# dc-motor-driver.net
KiCad netlist of a schematic drawn in EAGLE
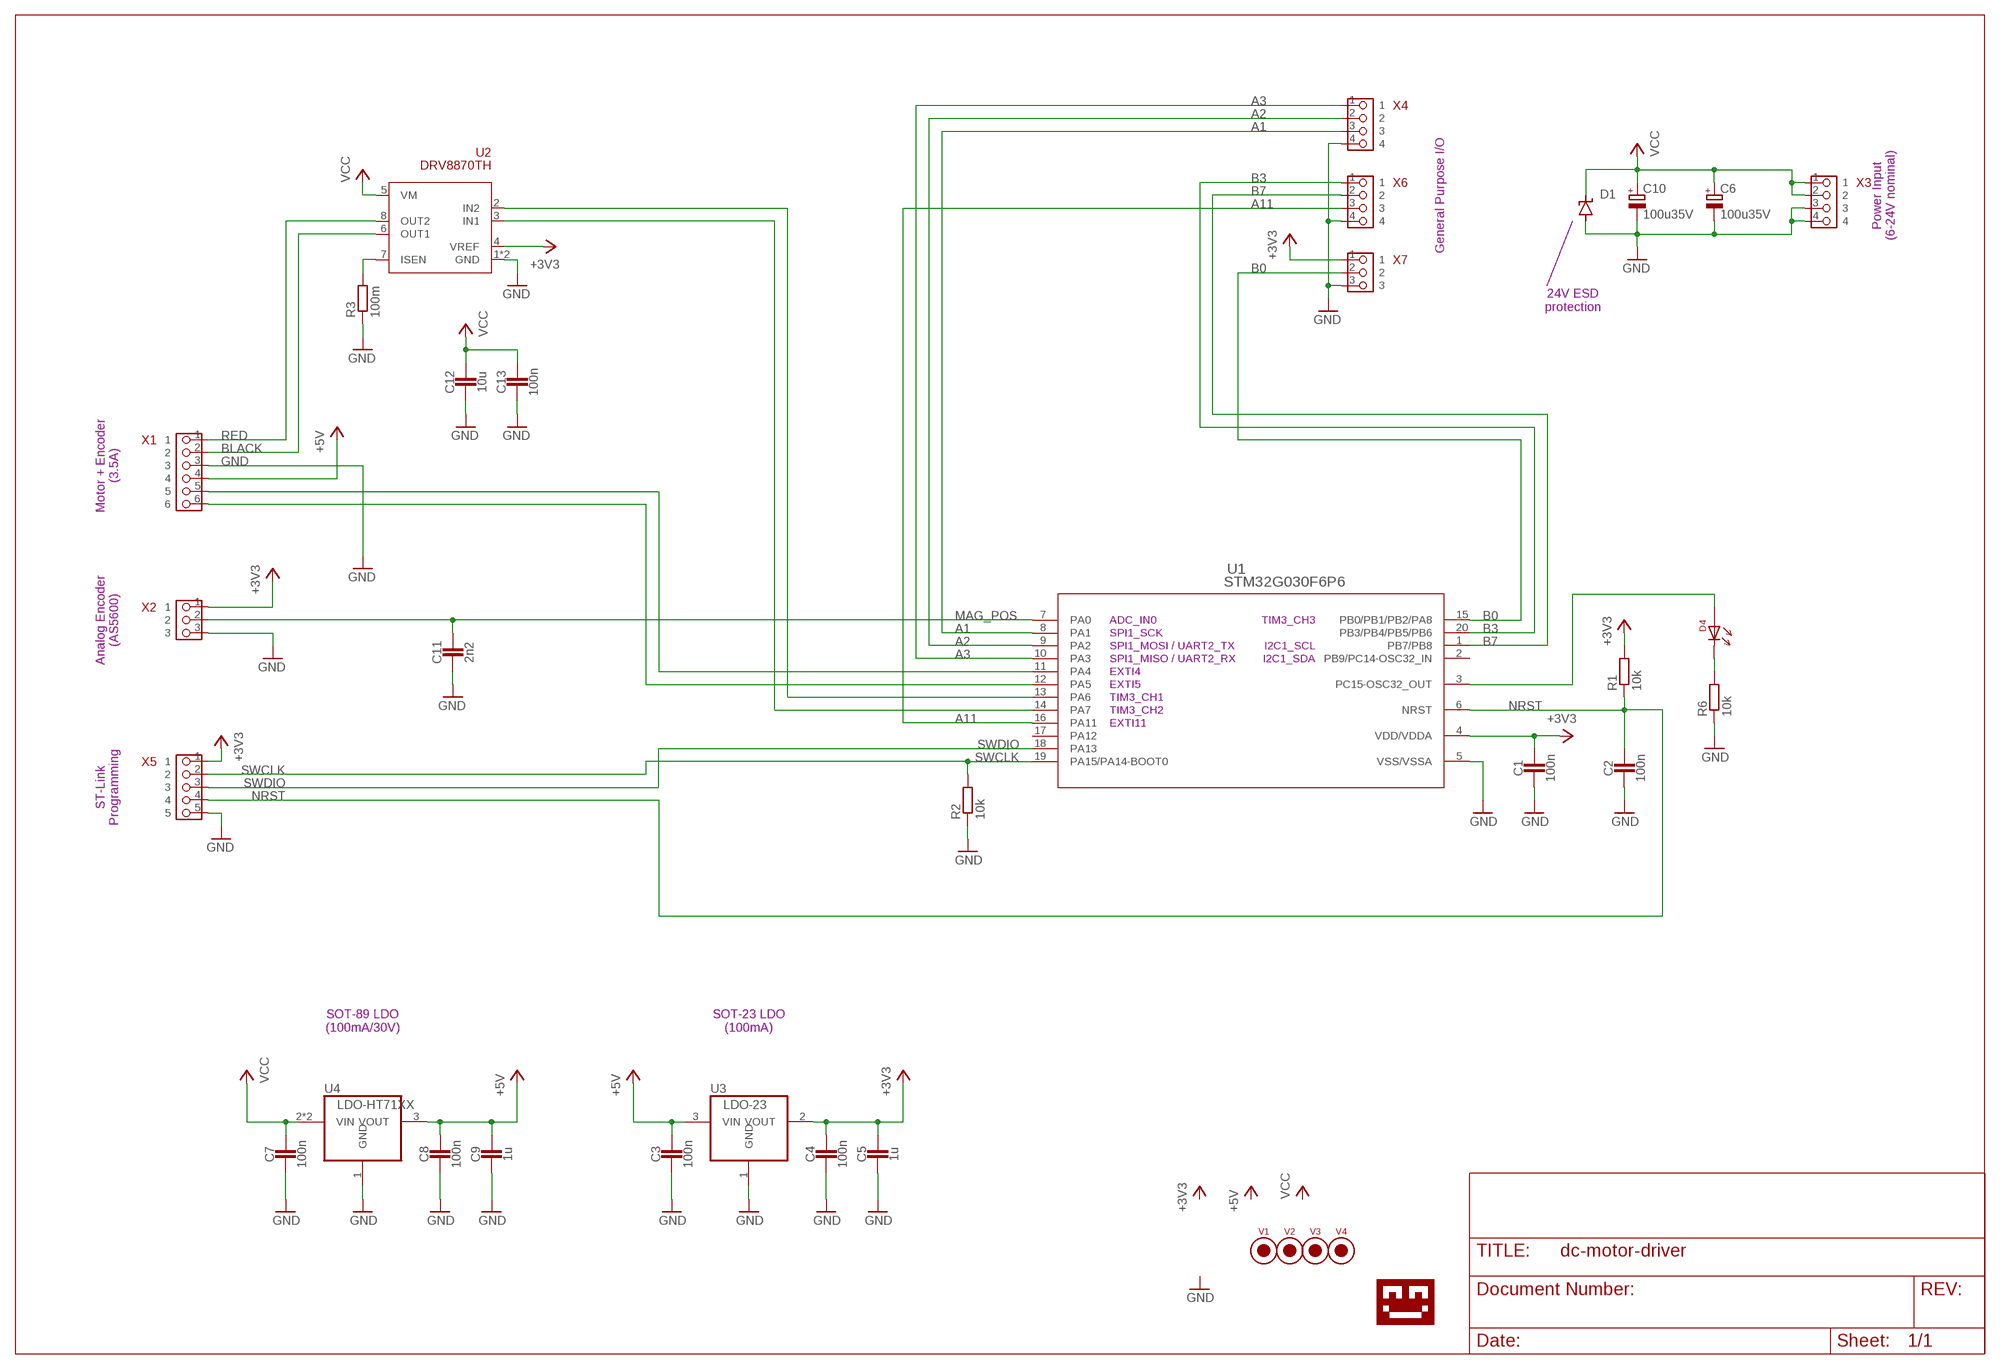
[diagram p0: schematic, sheet 1]

(export (version "E")
  (design (tool "Eeschema 10.0.6"))
  (components
    (comp (ref "C1")
      (value "100n")
      (footprint "eagle-import:0603_CAP")
      (libsource (lib "eagle-import") (part "CAPACITOR0603_CAP"))
    )
    (comp (ref "C2")
      (value "100n")
      (footprint "eagle-import:0603_CAP")
      (libsource (lib "eagle-import") (part "CAPACITOR0603_CAP"))
    )
    (comp (ref "C3")
      (value "100n")
      (footprint "eagle-import:0603_CAP")
      (libsource (lib "eagle-import") (part "CAPACITOR0603_CAP"))
    )
    (comp (ref "C4")
      (value "100n")
      (footprint "eagle-import:0603_CAP")
      (libsource (lib "eagle-import") (part "CAPACITOR0603_CAP"))
    )
    (comp (ref "C5")
      (value "1u")
      (footprint "eagle-import:0603_CAP")
      (libsource (lib "eagle-import") (part "CAPACITOR0603_CAP"))
    )
    (comp (ref "C6")
      (value "100u35V")
      (footprint "eagle-import:153CLV-0605")
      (libsource (lib "eagle-import") (part "CPOL-EU153CLV-0605"))
    )
    (comp (ref "C7")
      (value "100n")
      (footprint "eagle-import:0603_CAP")
      (libsource (lib "eagle-import") (part "CAPACITOR0603_CAP"))
    )
    (comp (ref "C8")
      (value "100n")
      (footprint "eagle-import:0603_CAP")
      (libsource (lib "eagle-import") (part "CAPACITOR0603_CAP"))
    )
    (comp (ref "C9")
      (value "1u")
      (footprint "eagle-import:0603_CAP")
      (libsource (lib "eagle-import") (part "CAPACITOR0603_CAP"))
    )
    (comp (ref "C10")
      (value "100u35V")
      (footprint "eagle-import:153CLV-0605")
      (libsource (lib "eagle-import") (part "CPOL-EU153CLV-0605"))
    )
    (comp (ref "C11")
      (value "2n2")
      (footprint "eagle-import:0603_CAP")
      (libsource (lib "eagle-import") (part "CAPACITOR0603_CAP"))
    )
    (comp (ref "C12")
      (value "10u")
      (footprint "eagle-import:1206_CAP")
      (libsource (lib "eagle-import") (part "CAPACITOR1206_CAP"))
    )
    (comp (ref "C13")
      (value "100n")
      (footprint "eagle-import:0603_CAP")
      (libsource (lib "eagle-import") (part "CAPACITOR0603_CAP"))
    )
    (comp (ref "D1")
      (value "SUPPRESSOR-SMBJ")
      (footprint "eagle-import:SMBJ")
      (libsource (lib "eagle-import") (part "SUPPRESSOR-SMBJ"))
    )
    (comp (ref "D4")
      (value "LED-0805")
      (footprint "eagle-import:0805-DOT")
      (libsource (lib "eagle-import") (part "LED-0805"))
    )
    (comp (ref "R1")
      (value "10k")
      (footprint "eagle-import:0603-RES")
      (libsource (lib "eagle-import") (part "RESISTOR0603_RES"))
    )
    (comp (ref "R2")
      (value "10k")
      (footprint "eagle-import:0603-RES")
      (libsource (lib "eagle-import") (part "RESISTOR0603_RES"))
    )
    (comp (ref "R3")
      (value "100m")
      (footprint "eagle-import:1206_RES_HIGH_CLEARANCE")
      (libsource (lib "eagle-import") (part "RESISTOR1206_RES_HIGH_CLEARANCE"))
    )
    (comp (ref "R6")
      (value "10k")
      (footprint "eagle-import:0603-RES")
      (libsource (lib "eagle-import") (part "RESISTOR0603_RES"))
    )
    (comp (ref "U$1")
      (value "LOGO-TOBENG-4MM-FINISH")
      (footprint "eagle-import:TOBENG-4MM-FINISH")
      (libsource (lib "eagle-import") (part "LOGO-TOBENG-4MM-FINISH"))
    )
    (comp (ref "U1")
      (value "STM32G030F6P6")
      (footprint "eagle-import:TSSOP20")
      (fields (field (name "COPYRIGHT") "Copyright (C) 2024 Ultra Librarian. All rights reserved."))
      (libsource (lib "eagle-import") (part "STM32G030F6P6"))
    )
    (comp (ref "U2")
      (value "DRV8870TH")
      (footprint "eagle-import:SOIC-8-THERM")
      (libsource (lib "eagle-import") (part "DRV8870TH"))
    )
    (comp (ref "U3")
      (value "LDO-23")
      (footprint "eagle-import:SOT-23")
      (libsource (lib "eagle-import") (part "LDO-23"))
    )
    (comp (ref "U4")
      (value "LDO-HT71XX")
      (footprint "eagle-import:SOT-89")
      (libsource (lib "eagle-import") (part "LDO-HT71XX"))
    )
    (comp (ref "V1")
      (value "FIDUCIAL2MM")
      (footprint "eagle-import:FIDUCIAL_2MM")
      (libsource (lib "eagle-import") (part "FIDUCIAL2MM"))
    )
    (comp (ref "V2")
      (value "FIDUCIAL2MM")
      (footprint "eagle-import:FIDUCIAL_2MM")
      (libsource (lib "eagle-import") (part "FIDUCIAL2MM"))
    )
    (comp (ref "V3")
      (value "FIDUCIAL2MM")
      (footprint "eagle-import:FIDUCIAL_2MM")
      (libsource (lib "eagle-import") (part "FIDUCIAL2MM"))
    )
    (comp (ref "V4")
      (value "FIDUCIAL2MM")
      (footprint "eagle-import:FIDUCIAL_2MM")
      (libsource (lib "eagle-import") (part "FIDUCIAL2MM"))
    )
    (comp (ref "X1")
      (value "PIN_6X1HD")
      (footprint "eagle-import:PIN_6X1_HD")
      (libsource (lib "eagle-import") (part "PIN_6X1HD"))
    )
    (comp (ref "X2")
      (value "PIN_3X1HD")
      (footprint "eagle-import:PIN_3X1_HD")
      (libsource (lib "eagle-import") (part "PIN_3X1HD"))
    )
    (comp (ref "X3")
      (value "PIN_4X1HD")
      (footprint "eagle-import:PIN_4X1_HD")
      (libsource (lib "eagle-import") (part "PIN_4X1HD"))
    )
    (comp (ref "X4")
      (value "PIN_4X1HD")
      (footprint "eagle-import:PIN_4X1_HD")
      (libsource (lib "eagle-import") (part "PIN_4X1HD"))
    )
    (comp (ref "X5")
      (value "PIN_5X1HD")
      (footprint "eagle-import:PIN_5X1_HD")
      (libsource (lib "eagle-import") (part "PIN_5X1HD"))
    )
    (comp (ref "X6")
      (value "PIN_4X1HD")
      (footprint "eagle-import:PIN_4X1_HD")
      (libsource (lib "eagle-import") (part "PIN_4X1HD"))
    )
    (comp (ref "X7")
      (value "PIN_3X1HD")
      (footprint "eagle-import:PIN_3X1_HD")
      (libsource (lib "eagle-import") (part "PIN_3X1HD"))
    )
  )
  (nets
    (net (code "1") (name "+3V3") (class "Default")
      (node (ref "C1") (pin "1") (pinfunction "1_1") (pintype "bidirectional"))
      (node (ref "C4") (pin "1") (pinfunction "1_1") (pintype "bidirectional"))
      (node (ref "C5") (pin "1") (pinfunction "1_1") (pintype "bidirectional"))
      (node (ref "R1") (pin "2") (pinfunction "2_2") (pintype "passive"))
      (node (ref "U1") (pin "4") (pinfunction "VDD/VDDA_4") (pintype "power_in"))
      (node (ref "U2") (pin "4") (pinfunction "VREF_4") (pintype "bidirectional"))
      (node (ref "U3") (pin "2") (pinfunction "VOUT_2") (pintype "output"))
      (node (ref "X2") (pin "1") (pinfunction "1_1") (pintype "bidirectional"))
      (node (ref "X5") (pin "1") (pinfunction "1_1") (pintype "bidirectional"))
      (node (ref "X7") (pin "1") (pinfunction "1_1") (pintype "bidirectional"))
    )
    (net (code "2") (name "+5V") (class "Default")
      (node (ref "C3") (pin "1") (pinfunction "1_1") (pintype "bidirectional"))
      (node (ref "C8") (pin "1") (pinfunction "1_1") (pintype "bidirectional"))
      (node (ref "C9") (pin "1") (pinfunction "1_1") (pintype "bidirectional"))
      (node (ref "U3") (pin "3") (pinfunction "VIN_3") (pintype "input"))
      (node (ref "U4") (pin "3") (pinfunction "VOUT_3") (pintype "output"))
      (node (ref "X1") (pin "4") (pinfunction "4_4") (pintype "bidirectional"))
    )
    (net (code "3") (name "/A1") (class "Default")
      (node (ref "U1") (pin "8") (pinfunction "PA1_8") (pintype "bidirectional"))
      (node (ref "X4") (pin "3") (pinfunction "3_3") (pintype "bidirectional"))
    )
    (net (code "4") (name "/A2") (class "Default")
      (node (ref "U1") (pin "9") (pinfunction "PA2_9") (pintype "bidirectional"))
      (node (ref "X4") (pin "2") (pinfunction "2_2") (pintype "bidirectional"))
    )
    (net (code "5") (name "/A3") (class "Default")
      (node (ref "U1") (pin "10") (pinfunction "PA3_10") (pintype "bidirectional"))
      (node (ref "X4") (pin "1") (pinfunction "1_1") (pintype "bidirectional"))
    )
    (net (code "6") (name "/A11") (class "Default")
      (node (ref "U1") (pin "16") (pinfunction "PA11_16") (pintype "bidirectional"))
      (node (ref "X6") (pin "3") (pinfunction "3_3") (pintype "bidirectional"))
    )
    (net (code "7") (name "/B0") (class "Default")
      (node (ref "U1") (pin "15") (pinfunction "PB0/PB1/PB2/PA8_15") (pintype "bidirectional"))
      (node (ref "X7") (pin "2") (pinfunction "2_2") (pintype "bidirectional"))
    )
    (net (code "8") (name "/B3") (class "Default")
      (node (ref "U1") (pin "20") (pinfunction "PB3/PB4/PB5/PB6_20") (pintype "bidirectional"))
      (node (ref "X6") (pin "1") (pinfunction "1_1") (pintype "bidirectional"))
    )
    (net (code "9") (name "/B7") (class "Default")
      (node (ref "U1") (pin "1") (pinfunction "PB7/PB8_1") (pintype "bidirectional"))
      (node (ref "X6") (pin "2") (pinfunction "2_2") (pintype "bidirectional"))
    )
    (net (code "10") (name "/BLACK") (class "Default")
      (node (ref "U2") (pin "6") (pinfunction "OUT1_6") (pintype "bidirectional"))
      (node (ref "X1") (pin "2") (pinfunction "2_2") (pintype "bidirectional"))
    )
    (net (code "11") (name "/MAG_POS") (class "Default")
      (node (ref "C11") (pin "1") (pinfunction "1_1") (pintype "bidirectional"))
      (node (ref "U1") (pin "7") (pinfunction "PA0_7") (pintype "bidirectional"))
      (node (ref "X2") (pin "2") (pinfunction "2_2") (pintype "bidirectional"))
    )
    (net (code "12") (name "/NRST") (class "Default")
      (node (ref "C2") (pin "1") (pinfunction "1_1") (pintype "bidirectional"))
      (node (ref "R1") (pin "1") (pinfunction "1_1") (pintype "passive"))
      (node (ref "U1") (pin "6") (pinfunction "NRST_6") (pintype "bidirectional"))
      (node (ref "X5") (pin "4") (pinfunction "4_4") (pintype "bidirectional"))
    )
    (net (code "13") (name "/RED") (class "Default")
      (node (ref "U2") (pin "8") (pinfunction "OUT2_8") (pintype "bidirectional"))
      (node (ref "X1") (pin "1") (pinfunction "1_1") (pintype "bidirectional"))
    )
    (net (code "14") (name "/SWCLK") (class "Default")
      (node (ref "R2") (pin "2") (pinfunction "2_2") (pintype "passive"))
      (node (ref "U1") (pin "19") (pinfunction "PA15/PA14-BOOT0_19") (pintype "bidirectional"))
      (node (ref "X5") (pin "2") (pinfunction "2_2") (pintype "bidirectional"))
    )
    (net (code "15") (name "/SWDIO") (class "Default")
      (node (ref "U1") (pin "18") (pinfunction "PA13_18") (pintype "bidirectional"))
      (node (ref "X5") (pin "3") (pinfunction "3_3") (pintype "bidirectional"))
    )
    (net (code "16") (name "GND") (class "Default")
      (node (ref "C1") (pin "2") (pinfunction "2_2") (pintype "bidirectional"))
      (node (ref "C10") (pin "-") (pinfunction "-_-") (pintype "passive"))
      (node (ref "C11") (pin "2") (pinfunction "2_2") (pintype "bidirectional"))
      (node (ref "C12") (pin "2") (pinfunction "2_2") (pintype "bidirectional"))
      (node (ref "C13") (pin "2") (pinfunction "2_2") (pintype "bidirectional"))
      (node (ref "C2") (pin "2") (pinfunction "2_2") (pintype "bidirectional"))
      (node (ref "C3") (pin "2") (pinfunction "2_2") (pintype "bidirectional"))
      (node (ref "C4") (pin "2") (pinfunction "2_2") (pintype "bidirectional"))
      (node (ref "C5") (pin "2") (pinfunction "2_2") (pintype "bidirectional"))
      (node (ref "C6") (pin "-") (pinfunction "-_-") (pintype "passive"))
      (node (ref "C7") (pin "2") (pinfunction "2_2") (pintype "bidirectional"))
      (node (ref "C8") (pin "2") (pinfunction "2_2") (pintype "bidirectional"))
      (node (ref "C9") (pin "2") (pinfunction "2_2") (pintype "bidirectional"))
      (node (ref "D1") (pin "A") (pinfunction "A_A") (pintype "passive"))
      (node (ref "R2") (pin "1") (pinfunction "1_1") (pintype "passive"))
      (node (ref "R3") (pin "1") (pinfunction "1_1") (pintype "passive"))
      (node (ref "R6") (pin "1") (pinfunction "1_1") (pintype "passive"))
      (node (ref "U1") (pin "5") (pinfunction "VSS/VSSA_5") (pintype "power_in"))
      (node (ref "U2") (pin "1") (pinfunction "GND_1") (pintype "bidirectional"))
      (node (ref "U2") (pin "9") (pinfunction "GND_9") (pintype "bidirectional"))
      (node (ref "U3") (pin "1") (pinfunction "GND_1") (pintype "power_in"))
      (node (ref "U4") (pin "1") (pinfunction "GND_1") (pintype "power_in"))
      (node (ref "X1") (pin "3") (pinfunction "3_3") (pintype "bidirectional"))
      (node (ref "X2") (pin "3") (pinfunction "3_3") (pintype "bidirectional"))
      (node (ref "X3") (pin "3") (pinfunction "3_3") (pintype "bidirectional"))
      (node (ref "X3") (pin "4") (pinfunction "4_4") (pintype "bidirectional"))
      (node (ref "X4") (pin "4") (pinfunction "4_4") (pintype "bidirectional"))
      (node (ref "X5") (pin "5") (pinfunction "5_5") (pintype "bidirectional"))
      (node (ref "X6") (pin "4") (pinfunction "4_4") (pintype "bidirectional"))
      (node (ref "X7") (pin "3") (pinfunction "3_3") (pintype "bidirectional"))
    )
    (net (code "17") (name "Net-(D4-Pad2)") (class "Default")
      (node (ref "D4") (pin "2") (pinfunction "2_2") (pintype "bidirectional"))
      (node (ref "R6") (pin "2") (pinfunction "2_2") (pintype "passive"))
    )
    (net (code "18") (name "Net-(U1-PA4)") (class "Default")
      (node (ref "U1") (pin "11") (pinfunction "PA4_11") (pintype "bidirectional"))
      (node (ref "X1") (pin "5") (pinfunction "5_5") (pintype "bidirectional"))
    )
    (net (code "19") (name "Net-(U1-PA5)") (class "Default")
      (node (ref "U1") (pin "12") (pinfunction "PA5_12") (pintype "bidirectional"))
      (node (ref "X1") (pin "6") (pinfunction "6_6") (pintype "bidirectional"))
    )
    (net (code "20") (name "Net-(U1-PA6)") (class "Default")
      (node (ref "U1") (pin "13") (pinfunction "PA6_13") (pintype "bidirectional"))
      (node (ref "U2") (pin "2") (pinfunction "IN2_2") (pintype "bidirectional"))
    )
    (net (code "21") (name "Net-(U1-PA7)") (class "Default")
      (node (ref "U1") (pin "14") (pinfunction "PA7_14") (pintype "bidirectional"))
      (node (ref "U2") (pin "3") (pinfunction "IN1_3") (pintype "bidirectional"))
    )
    (net (code "22") (name "Net-(U1-PC15-OSC32_OUT)") (class "Default")
      (node (ref "D4") (pin "1") (pinfunction "1_1") (pintype "bidirectional"))
      (node (ref "U1") (pin "3") (pinfunction "PC15-OSC32_OUT_3") (pintype "bidirectional"))
    )
    (net (code "23") (name "Net-(U2-ISEN)") (class "Default")
      (node (ref "R3") (pin "2") (pinfunction "2_2") (pintype "passive"))
      (node (ref "U2") (pin "7") (pinfunction "ISEN_7") (pintype "bidirectional"))
    )
    (net (code "24") (name "VCC") (class "Default")
      (node (ref "C10") (pin "+") (pinfunction "+_+") (pintype "passive"))
      (node (ref "C12") (pin "1") (pinfunction "1_1") (pintype "bidirectional"))
      (node (ref "C13") (pin "1") (pinfunction "1_1") (pintype "bidirectional"))
      (node (ref "C6") (pin "+") (pinfunction "+_+") (pintype "passive"))
      (node (ref "C7") (pin "1") (pinfunction "1_1") (pintype "bidirectional"))
      (node (ref "D1") (pin "C") (pinfunction "C_C") (pintype "passive"))
      (node (ref "U2") (pin "5") (pinfunction "VM_5") (pintype "bidirectional"))
      (node (ref "U4") (pin "2") (pinfunction "VIN_2") (pintype "input"))
      (node (ref "U4") (pin "2@1") (pinfunction "VIN_2@1") (pintype "input"))
      (node (ref "X3") (pin "1") (pinfunction "1_1") (pintype "bidirectional"))
      (node (ref "X3") (pin "2") (pinfunction "2_2") (pintype "bidirectional"))
    )
    (net (code "25") (name "unconnected-(U1-PA12-Pad17)") (class "Default")
      (node (ref "U1") (pin "17") (pinfunction "PA12_17") (pintype "bidirectional"))
    )
    (net (code "26") (name "unconnected-(U1-PB9{slash}PC14-OSC32_IN-Pad2)") (class "Default")
      (node (ref "U1") (pin "2") (pinfunction "PB9/PC14-OSC32_IN_2") (pintype "bidirectional"))
    )
  )
)
